# EspProg.net
KiCad netlist of a schematic drawn in Altium Designer
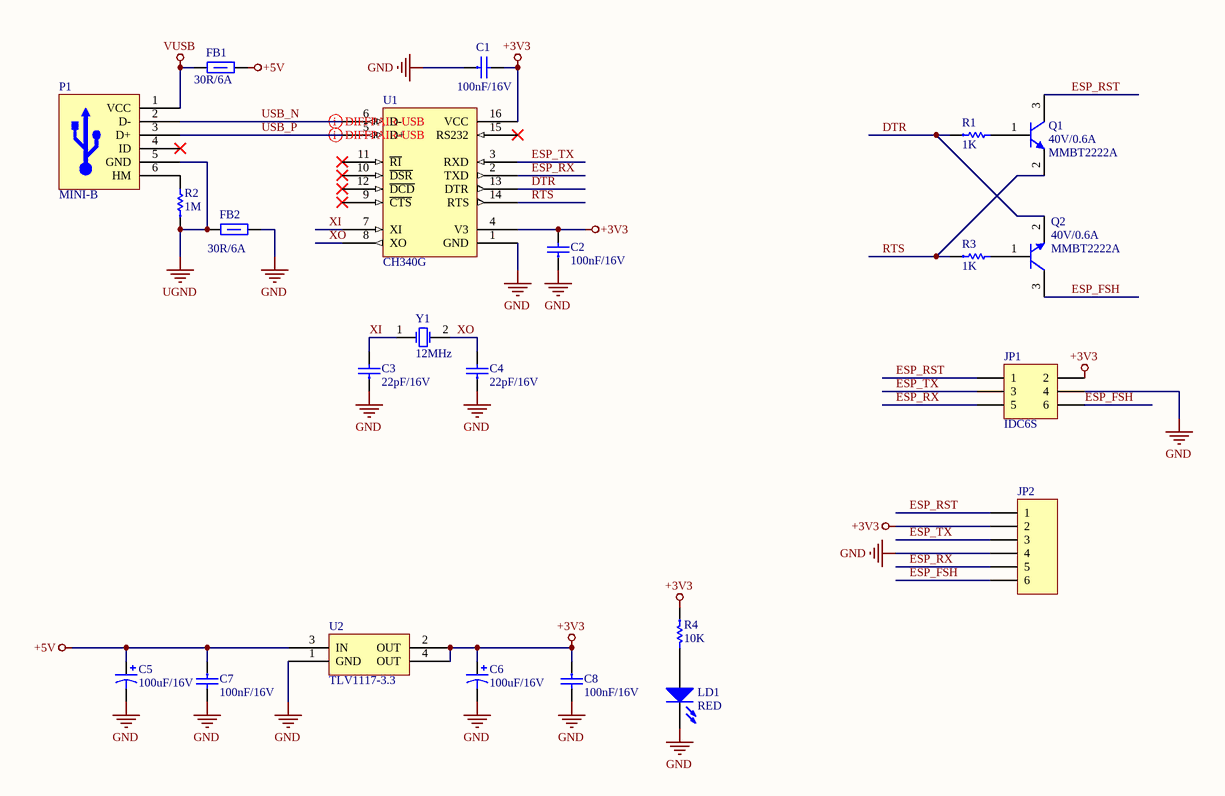
[diagram p0: EspProg.SchDoc]

(export (version "E")
  (design (tool "Eeschema 10.0.6"))
  (components
    (comp (ref "C1")
      (value "100nF/16V")
      (footprint "CAP-CER0603-0.8H")
      (description "CAP CER 100nF/16V 10% X7R 0603 SMD")
      (fields (field (name "MFR") "YAGEO"))
      (libsource (lib "ADLibEP") (part "CAPCER0008 0603 100nF/16V"))
    )
    (comp (ref "C2")
      (value "100nF/16V")
      (footprint "CAP-CER0603-0.8H")
      (description "CAP CER 100nF/16V 10% X7R 0603 SMD")
      (fields (field (name "MFR") "YAGEO"))
      (libsource (lib "ADLibEP") (part "CAPCER0008 0603 100nF/16V"))
    )
    (comp (ref "C3")
      (value "22pF/16V")
      (footprint "CAP-CER0603-0.8H")
      (description "CAP CER 22pF/16V 5% C0G 0603 SMD")
      (fields (field (name "MFR") "KEMET"))
      (libsource (lib "ADLibEP") (part "CAPCER0060 0603 22pF/16V"))
    )
    (comp (ref "C4")
      (value "22pF/16V")
      (footprint "CAP-CER0603-0.8H")
      (description "CAP CER 22pF/16V 5% C0G 0603 SMD")
      (fields (field (name "MFR") "KEMET"))
      (libsource (lib "ADLibEP") (part "CAPCER0060 0603 22pF/16V"))
    )
    (comp (ref "C5")
      (value "100uF/16V")
      (footprint "CAP-ALU-6.3D5.8H-SMD")
      (description "CAP ALU 100uF/16V 20% 2K105 2.2P 6.3X5.8 SMD")
      (fields (field (name "MFR") "NICHICON"))
      (libsource (lib "ADLibEP") (part "CAPALU0012 6.3X5.8 100uF/16V SMD"))
    )
    (comp (ref "C6")
      (value "100uF/16V")
      (footprint "CAP-ALU-6.3D5.8H-SMD")
      (description "CAP ALU 100uF/16V 20% 2K105 2.2P 6.3X5.8 SMD")
      (fields (field (name "MFR") "NICHICON"))
      (libsource (lib "ADLibEP") (part "CAPALU0012 6.3X5.8 100uF/16V SMD"))
    )
    (comp (ref "C7")
      (value "100nF/16V")
      (footprint "CAP-CER0603-0.8H")
      (description "CAP CER 100nF/16V 10% X7R 0603 SMD")
      (fields (field (name "MFR") "YAGEO"))
      (libsource (lib "ADLibEP") (part "CAPCER0008 0603 100nF/16V"))
    )
    (comp (ref "C8")
      (value "100nF/16V")
      (footprint "CAP-CER0603-0.8H")
      (description "CAP CER 100nF/16V 10% X7R 0603 SMD")
      (fields (field (name "MFR") "YAGEO"))
      (libsource (lib "ADLibEP") (part "CAPCER0008 0603 100nF/16V"))
    )
    (comp (ref "FB1")
      (value "30R/6A")
      (footprint "IND-C0805-1.1H")
      (description "FIL FER CHP 1LN 120R 3A 0805 SMD")
      (fields (field (name "MFR") "MURATA"))
      (libsource (lib "ADLibEP") (part "FILFER0001 0805 120R/3A"))
    )
    (comp (ref "FB2")
      (value "30R/6A")
      (footprint "IND-C0805-1.1H")
      (description "FIL FER CHP 1LN 120R 3A 0805 SMD")
      (fields (field (name "MFR") "MURATA"))
      (libsource (lib "ADLibEP") (part "FILFER0001 0805 120R/3A"))
    )
    (comp (ref "JP1")
      (value "IDC6S")
      (footprint "CON-IDC6-2.54P9.3H-S-THR")
      (description "CON W2B IDC2.54M-2X3V-9H THR")
      (fields (field (name "MFR") "XFCN"))
      (libsource (lib "ADLibEP") (part "CONW2B0010 IDC2.54M-6PV"))
    )
    (comp (ref "JP2")
      (value "XH2.54M-1X06V-7H")
      (footprint "CON-XH2.54-6S")
      (description "CON B2B XH2.54M-1X06V-7H THR")
      (fields (field (name "MFR") "XUNPU"))
      (libsource (lib "ADLibEP") (part "CONW2B0005 XH2.54M-1X06V-7H"))
    )
    (comp (ref "LD1")
      (value "RED")
      (footprint "LED-IND0603-RED-0.6H")
      (description "LED IND RED CLR 2V 20mA 0603 SMD")
      (fields (field (name "MFR") "WURTH"))
      (libsource (lib "ADLibEP") (part "LEDIND0001 0603 RED"))
    )
    (comp (ref "P1")
      (value "MINI-B")
      (footprint "CON-USB-MINIB-SMD")
      (description "CON USB V20 MBF1 SMD")
      (libsource (lib "ADLibEP") (part "CONUSB0000 USB2.0 MINI-B"))
    )
    (comp (ref "Q1")
      (value "40V/0.6A")
      (footprint "SOT23-3-1.1H")
      (description "BJT NPN 40V 0.6A SOT23-3 SMD")
      (fields (field (name "NOTE") "MMBT2222A") (field (name "MFR") "ONSEMI"))
      (libsource (lib "ADLibEP") (part "BJTNPN0001 SOT23 40V/0.6A"))
    )
    (comp (ref "Q2")
      (value "40V/0.6A")
      (footprint "SOT23-3-1.1H")
      (description "BJT NPN 40V 0.6A SOT23-3 SMD")
      (fields (field (name "NOTE") "MMBT2222A") (field (name "MFR") "ONSEMI"))
      (libsource (lib "ADLibEP") (part "BJTNPN0001 SOT23 40V/0.6A"))
    )
    (comp (ref "R1")
      (value "1K")
      (footprint "RES-CHP0603-0.6H")
      (description "RES CHP 1K 1% 1/10W 0603 SMD")
      (fields (field (name "MFR") "YAGEO"))
      (libsource (lib "ADLibEP") (part "RESCHP0007 0603 1% 1K"))
    )
    (comp (ref "R2")
      (value "1M")
      (footprint "RES-CHP0603-0.6H")
      (description "RES CHP 1M 1% 1/10W 0603 SMD")
      (fields (field (name "MFR") "YAGEO"))
      (libsource (lib "ADLibEP") (part "RESCHP0036 0603 1% 1M"))
    )
    (comp (ref "R3")
      (value "1K")
      (footprint "RES-CHP0603-0.6H")
      (description "RES CHP 1K 1% 1/10W 0603 SMD")
      (fields (field (name "MFR") "YAGEO"))
      (libsource (lib "ADLibEP") (part "RESCHP0007 0603 1% 1K"))
    )
    (comp (ref "R4")
      (value "10K")
      (footprint "RES-CHP0603-0.6H")
      (description "RES CHP 10K 1% 1/10W 0603 SMD")
      (fields (field (name "MFR") "YAGEO"))
      (libsource (lib "ADLibEP") (part "RESCHP0008 0603 1% 10K"))
    )
    (comp (ref "U1")
      (value "CH340G")
      (footprint "SOIC16-1.75H")
      (description "ICS INT USB-TTL CH340G 16SOIC SMD")
      (fields (field (name "MFR") "WCH"))
      (libsource (lib "ADLibEP") (part "ICSINT0001 CH340G"))
    )
    (comp (ref "U2")
      (value "TLV1117-3.3")
      (footprint "SOT223-4N-1.8H")
      (description "ICS VRE TLV1117-33 3V3 0.8A SOT223 SMD")
      (fields (field (name "MFR") "TI"))
      (libsource (lib "ADLibEP") (part "ICSVRE0001 SOT223 TLV1117-3.3"))
    )
    (comp (ref "Y1")
      (value "12MHz")
      (footprint "XTAL-HC49S-4.1H-SMD")
      (description "XTA CRY 12MHz 20pF 10PPM HC49S SMD")
      (fields (field (name "MFR") "YXC"))
      (libsource (lib "ADLibEP") (part "XTACRY0004 HC49S-SMD 12MHz"))
    )
  )
  (nets
    (net (code "1") (name "+3V3") (class "Default")
      (node (ref "C1") (pin "2") (pinfunction "2_2") (pintype "passive"))
      (node (ref "C2") (pin "2") (pinfunction "2_2") (pintype "passive"))
      (node (ref "C6") (pin "1") (pinfunction "1_1") (pintype "passive"))
      (node (ref "C8") (pin "1") (pinfunction "1_1") (pintype "passive"))
      (node (ref "JP1") (pin "2") (pinfunction "2_2") (pintype "passive"))
      (node (ref "JP2") (pin "2") (pinfunction "2_2") (pintype "passive"))
      (node (ref "R4") (pin "1") (pinfunction "1_1") (pintype "passive"))
      (node (ref "U1") (pin "16") (pinfunction "VCC_16") (pintype "power_in"))
      (node (ref "U1") (pin "4") (pinfunction "V3_4") (pintype "power_in"))
      (node (ref "U2") (pin "2") (pinfunction "OUT_2") (pintype "passive"))
      (node (ref "U2") (pin "4") (pinfunction "OUT_4") (pintype "passive"))
    )
    (net (code "2") (name "+5V") (class "Default")
      (node (ref "C5") (pin "1") (pinfunction "1_1") (pintype "passive"))
      (node (ref "C7") (pin "1") (pinfunction "1_1") (pintype "passive"))
      (node (ref "FB1") (pin "2") (pinfunction "2_2") (pintype "passive"))
      (node (ref "U2") (pin "3") (pinfunction "IN_3") (pintype "passive"))
    )
    (net (code "3") (name "/DTR") (class "Default")
      (node (ref "Q2") (pin "2") (pinfunction "E_2") (pintype "passive"))
      (node (ref "R1") (pin "1") (pinfunction "1_1") (pintype "passive"))
      (node (ref "U1") (pin "13") (pinfunction "DTR_13") (pintype "output"))
    )
    (net (code "4") (name "/ESP_FSH") (class "Default")
      (node (ref "JP1") (pin "6") (pinfunction "6_6") (pintype "passive"))
      (node (ref "JP2") (pin "6") (pinfunction "6_6") (pintype "passive"))
      (node (ref "Q2") (pin "3") (pinfunction "C_3") (pintype "passive"))
    )
    (net (code "5") (name "/ESP_RST") (class "Default")
      (node (ref "JP1") (pin "1") (pinfunction "1_1") (pintype "passive"))
      (node (ref "JP2") (pin "1") (pinfunction "1_1") (pintype "passive"))
      (node (ref "Q1") (pin "3") (pinfunction "C_3") (pintype "passive"))
    )
    (net (code "6") (name "/ESP_RX") (class "Default")
      (node (ref "JP1") (pin "5") (pinfunction "5_5") (pintype "passive"))
      (node (ref "JP2") (pin "5") (pinfunction "5_5") (pintype "passive"))
      (node (ref "U1") (pin "2") (pinfunction "TXD_2") (pintype "output"))
    )
    (net (code "7") (name "/ESP_TX") (class "Default")
      (node (ref "JP1") (pin "3") (pinfunction "3_3") (pintype "passive"))
      (node (ref "JP2") (pin "3") (pinfunction "3_3") (pintype "passive"))
      (node (ref "U1") (pin "3") (pinfunction "RXD_3") (pintype "input"))
    )
    (net (code "8") (name "/RTS") (class "Default")
      (node (ref "Q1") (pin "2") (pinfunction "E_2") (pintype "passive"))
      (node (ref "R3") (pin "1") (pinfunction "1_1") (pintype "passive"))
      (node (ref "U1") (pin "14") (pinfunction "RTS_14") (pintype "output"))
    )
    (net (code "9") (name "/USB_N") (class "Default")
      (node (ref "P1") (pin "2") (pinfunction "D-_2") (pintype "passive"))
      (node (ref "U1") (pin "6") (pinfunction "D-_6") (pintype "bidirectional"))
    )
    (net (code "10") (name "/USB_P") (class "Default")
      (node (ref "P1") (pin "3") (pinfunction "D+_3") (pintype "passive"))
      (node (ref "U1") (pin "5") (pinfunction "D+_5") (pintype "bidirectional"))
    )
    (net (code "11") (name "/XI") (class "Default")
      (node (ref "C3") (pin "2") (pinfunction "2_2") (pintype "passive"))
      (node (ref "U1") (pin "7") (pinfunction "XI_7") (pintype "input"))
      (node (ref "Y1") (pin "1") (pinfunction "OSC1_1") (pintype "passive"))
    )
    (net (code "12") (name "/XO") (class "Default")
      (node (ref "C4") (pin "2") (pinfunction "2_2") (pintype "passive"))
      (node (ref "U1") (pin "8") (pinfunction "XO_8") (pintype "output"))
      (node (ref "Y1") (pin "2") (pinfunction "OSC2_2") (pintype "passive"))
    )
    (net (code "13") (name "GND") (class "Default")
      (node (ref "C1") (pin "1") (pinfunction "1_1") (pintype "passive"))
      (node (ref "C2") (pin "1") (pinfunction "1_1") (pintype "passive"))
      (node (ref "C3") (pin "1") (pinfunction "1_1") (pintype "passive"))
      (node (ref "C4") (pin "1") (pinfunction "1_1") (pintype "passive"))
      (node (ref "C5") (pin "2") (pinfunction "2_2") (pintype "passive"))
      (node (ref "C6") (pin "2") (pinfunction "2_2") (pintype "passive"))
      (node (ref "C7") (pin "2") (pinfunction "2_2") (pintype "passive"))
      (node (ref "C8") (pin "2") (pinfunction "2_2") (pintype "passive"))
      (node (ref "FB2") (pin "2") (pinfunction "2_2") (pintype "passive"))
      (node (ref "JP1") (pin "4") (pinfunction "4_4") (pintype "passive"))
      (node (ref "JP2") (pin "4") (pinfunction "4_4") (pintype "passive"))
      (node (ref "LD1") (pin "2") (pinfunction "K_2") (pintype "passive"))
      (node (ref "U1") (pin "1") (pinfunction "GND_1") (pintype "power_in"))
      (node (ref "U2") (pin "1") (pinfunction "GND_1") (pintype "passive"))
    )
    (net (code "14") (name "Net-(LD1-A)") (class "Default")
      (node (ref "LD1") (pin "1") (pinfunction "A_1") (pintype "passive"))
      (node (ref "R4") (pin "2") (pinfunction "2_2") (pintype "passive"))
    )
    (net (code "15") (name "Net-(P1-HM)") (class "Default")
      (node (ref "P1") (pin "6") (pinfunction "HM_6") (pintype "passive"))
      (node (ref "R2") (pin "2") (pinfunction "2_2") (pintype "passive"))
    )
    (net (code "16") (name "Net-(Q1-B)") (class "Default")
      (node (ref "Q1") (pin "1") (pinfunction "B_1") (pintype "passive"))
      (node (ref "R1") (pin "2") (pinfunction "2_2") (pintype "passive"))
    )
    (net (code "17") (name "Net-(Q2-B)") (class "Default")
      (node (ref "Q2") (pin "1") (pinfunction "B_1") (pintype "passive"))
      (node (ref "R3") (pin "2") (pinfunction "2_2") (pintype "passive"))
    )
    (net (code "18") (name "UGND") (class "Default")
      (node (ref "FB2") (pin "1") (pinfunction "1_1") (pintype "passive"))
      (node (ref "P1") (pin "5") (pinfunction "GND_5") (pintype "passive"))
      (node (ref "R2") (pin "1") (pinfunction "1_1") (pintype "passive"))
    )
    (net (code "19") (name "VUSB") (class "Default")
      (node (ref "FB1") (pin "1") (pinfunction "1_1") (pintype "passive"))
      (node (ref "P1") (pin "1") (pinfunction "VCC_1") (pintype "passive"))
    )
    (net (code "20") (name "unconnected-(P1-ID-Pad4)") (class "Default")
      (node (ref "P1") (pin "4") (pinfunction "ID_4") (pintype "passive+no_connect"))
    )
    (net (code "21") (name "unconnected-(U1-RS232-Pad15)") (class "Default")
      (node (ref "U1") (pin "15") (pinfunction "RS232_15") (pintype "input+no_connect"))
    )
    (net (code "22") (name "unconnected-(U1-~{CTS}-Pad9)") (class "Default")
      (node (ref "U1") (pin "9") (pinfunction "~{CTS}_9") (pintype "input+no_connect"))
    )
    (net (code "23") (name "unconnected-(U1-~{DCD}-Pad12)") (class "Default")
      (node (ref "U1") (pin "12") (pinfunction "~{DCD}_12") (pintype "input+no_connect"))
    )
    (net (code "24") (name "unconnected-(U1-~{DSR}-Pad10)") (class "Default")
      (node (ref "U1") (pin "10") (pinfunction "~{DSR}_10") (pintype "input+no_connect"))
    )
    (net (code "25") (name "unconnected-(U1-~{RI}-Pad11)") (class "Default")
      (node (ref "U1") (pin "11") (pinfunction "~{RI}_11") (pintype "input+no_connect"))
    )
  )
)
